# Center_panel_V1_1.net
KiCad netlist of a schematic drawn in EAGLE
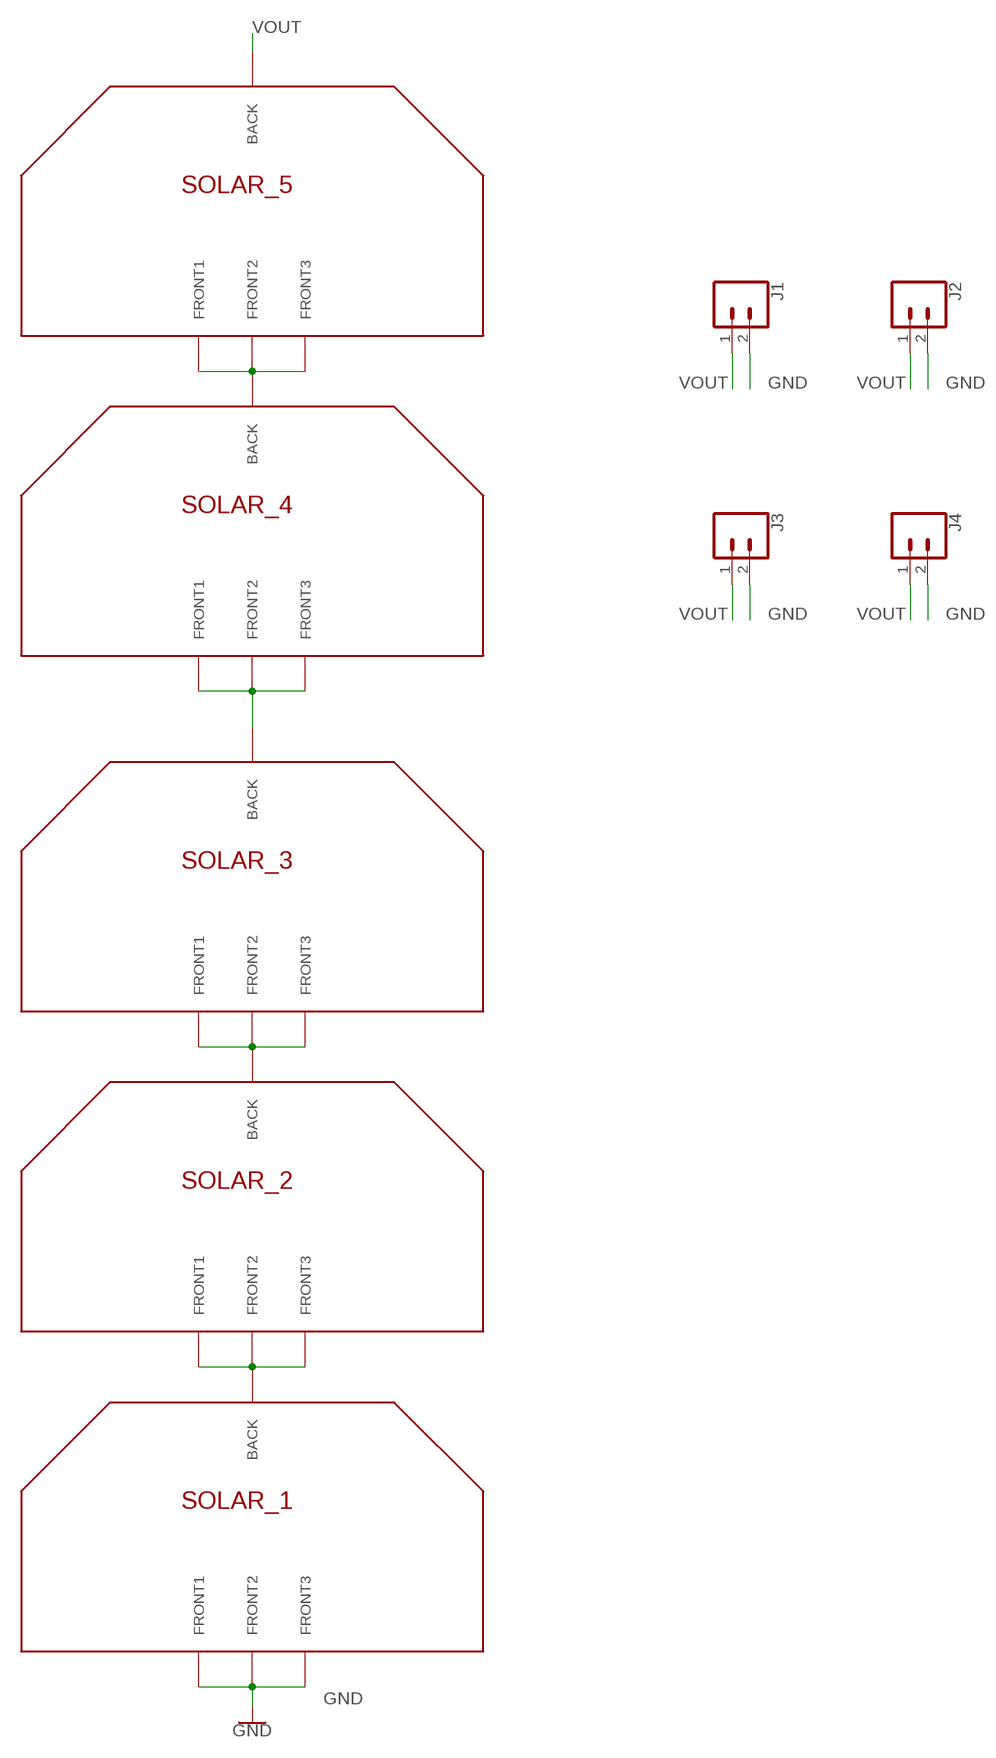
[diagram p0: schematic, sheet 1]

(export (version "E")
  (design (tool "Eeschema 10.0.6"))
  (components
    (comp (ref "J1")
      (value "CONN_02")
      (footprint "eagle-import:1X02")
      (libsource (lib "eagle-import") (part "CONN_02"))
    )
    (comp (ref "J2")
      (value "CONN_02")
      (footprint "eagle-import:1X02")
      (libsource (lib "eagle-import") (part "CONN_02"))
    )
    (comp (ref "J3")
      (value "CONN_02")
      (footprint "eagle-import:1X02")
      (libsource (lib "eagle-import") (part "CONN_02"))
    )
    (comp (ref "J4")
      (value "CONN_02")
      (footprint "eagle-import:1X02")
      (libsource (lib "eagle-import") (part "CONN_02"))
    )
    (comp (ref "SOLAR_1")
      (value "SOLAR_CELL_HALF_TABS")
      (footprint "eagle-import:SOLAR_CELL_3G30A_HALF_TAB")
      (libsource (lib "eagle-import") (part "SOLAR_CELL_HALF_TABS"))
    )
    (comp (ref "SOLAR_2")
      (value "SOLAR_CELL_HALF_TABS")
      (footprint "eagle-import:SOLAR_CELL_3G30A_HALF_TAB")
      (libsource (lib "eagle-import") (part "SOLAR_CELL_HALF_TABS"))
    )
    (comp (ref "SOLAR_3")
      (value "SOLAR_CELL_HALF_TABS")
      (footprint "eagle-import:SOLAR_CELL_3G30A_HALF_TAB")
      (libsource (lib "eagle-import") (part "SOLAR_CELL_HALF_TABS"))
    )
    (comp (ref "SOLAR_4")
      (value "SOLAR_CELL_HALF_TABS")
      (footprint "eagle-import:SOLAR_CELL_3G30A_HALF_TAB")
      (libsource (lib "eagle-import") (part "SOLAR_CELL_HALF_TABS"))
    )
    (comp (ref "SOLAR_5")
      (value "SOLAR_CELL_HALF_TABS")
      (footprint "eagle-import:SOLAR_CELL_3G30A_HALF_TAB")
      (libsource (lib "eagle-import") (part "SOLAR_CELL_HALF_TABS"))
    )
  )
  (nets
    (net (code "1") (name "/VOUT") (class "Default")
      (node (ref "J1") (pin "1") (pinfunction "1_1") (pintype "passive"))
      (node (ref "J2") (pin "1") (pinfunction "1_1") (pintype "passive"))
      (node (ref "J3") (pin "1") (pinfunction "1_1") (pintype "passive"))
      (node (ref "J4") (pin "1") (pinfunction "1_1") (pintype "passive"))
      (node (ref "SOLAR_5") (pin "P$1") (pinfunction "BACK_P$1") (pintype "bidirectional"))
    )
    (net (code "2") (name "GND") (class "Default")
      (node (ref "J1") (pin "2") (pinfunction "2_2") (pintype "passive"))
      (node (ref "J2") (pin "2") (pinfunction "2_2") (pintype "passive"))
      (node (ref "J3") (pin "2") (pinfunction "2_2") (pintype "passive"))
      (node (ref "J4") (pin "2") (pinfunction "2_2") (pintype "passive"))
      (node (ref "SOLAR_1") (pin "P$F1") (pinfunction "FRONT1_P$F1") (pintype "bidirectional"))
      (node (ref "SOLAR_1") (pin "P$F2") (pinfunction "FRONT2_P$F2") (pintype "bidirectional"))
      (node (ref "SOLAR_1") (pin "P$F3") (pinfunction "FRONT3_P$F3") (pintype "bidirectional"))
    )
    (net (code "3") (name "Net-(SOLAR_1-BACK)") (class "Default")
      (node (ref "SOLAR_1") (pin "P$1") (pinfunction "BACK_P$1") (pintype "bidirectional"))
      (node (ref "SOLAR_2") (pin "P$F1") (pinfunction "FRONT1_P$F1") (pintype "bidirectional"))
      (node (ref "SOLAR_2") (pin "P$F2") (pinfunction "FRONT2_P$F2") (pintype "bidirectional"))
      (node (ref "SOLAR_2") (pin "P$F3") (pinfunction "FRONT3_P$F3") (pintype "bidirectional"))
    )
    (net (code "4") (name "Net-(SOLAR_2-BACK)") (class "Default")
      (node (ref "SOLAR_2") (pin "P$1") (pinfunction "BACK_P$1") (pintype "bidirectional"))
      (node (ref "SOLAR_3") (pin "P$F1") (pinfunction "FRONT1_P$F1") (pintype "bidirectional"))
      (node (ref "SOLAR_3") (pin "P$F2") (pinfunction "FRONT2_P$F2") (pintype "bidirectional"))
      (node (ref "SOLAR_3") (pin "P$F3") (pinfunction "FRONT3_P$F3") (pintype "bidirectional"))
    )
    (net (code "5") (name "Net-(SOLAR_3-BACK)") (class "Default")
      (node (ref "SOLAR_3") (pin "P$1") (pinfunction "BACK_P$1") (pintype "bidirectional"))
      (node (ref "SOLAR_4") (pin "P$F1") (pinfunction "FRONT1_P$F1") (pintype "bidirectional"))
      (node (ref "SOLAR_4") (pin "P$F2") (pinfunction "FRONT2_P$F2") (pintype "bidirectional"))
      (node (ref "SOLAR_4") (pin "P$F3") (pinfunction "FRONT3_P$F3") (pintype "bidirectional"))
    )
    (net (code "6") (name "Net-(SOLAR_4-BACK)") (class "Default")
      (node (ref "SOLAR_4") (pin "P$1") (pinfunction "BACK_P$1") (pintype "bidirectional"))
      (node (ref "SOLAR_5") (pin "P$F1") (pinfunction "FRONT1_P$F1") (pintype "bidirectional"))
      (node (ref "SOLAR_5") (pin "P$F2") (pinfunction "FRONT2_P$F2") (pintype "bidirectional"))
      (node (ref "SOLAR_5") (pin "P$F3") (pinfunction "FRONT3_P$F3") (pintype "bidirectional"))
    )
  )
)
